# USB.net
KiCad netlist of a schematic drawn in Altium Designer
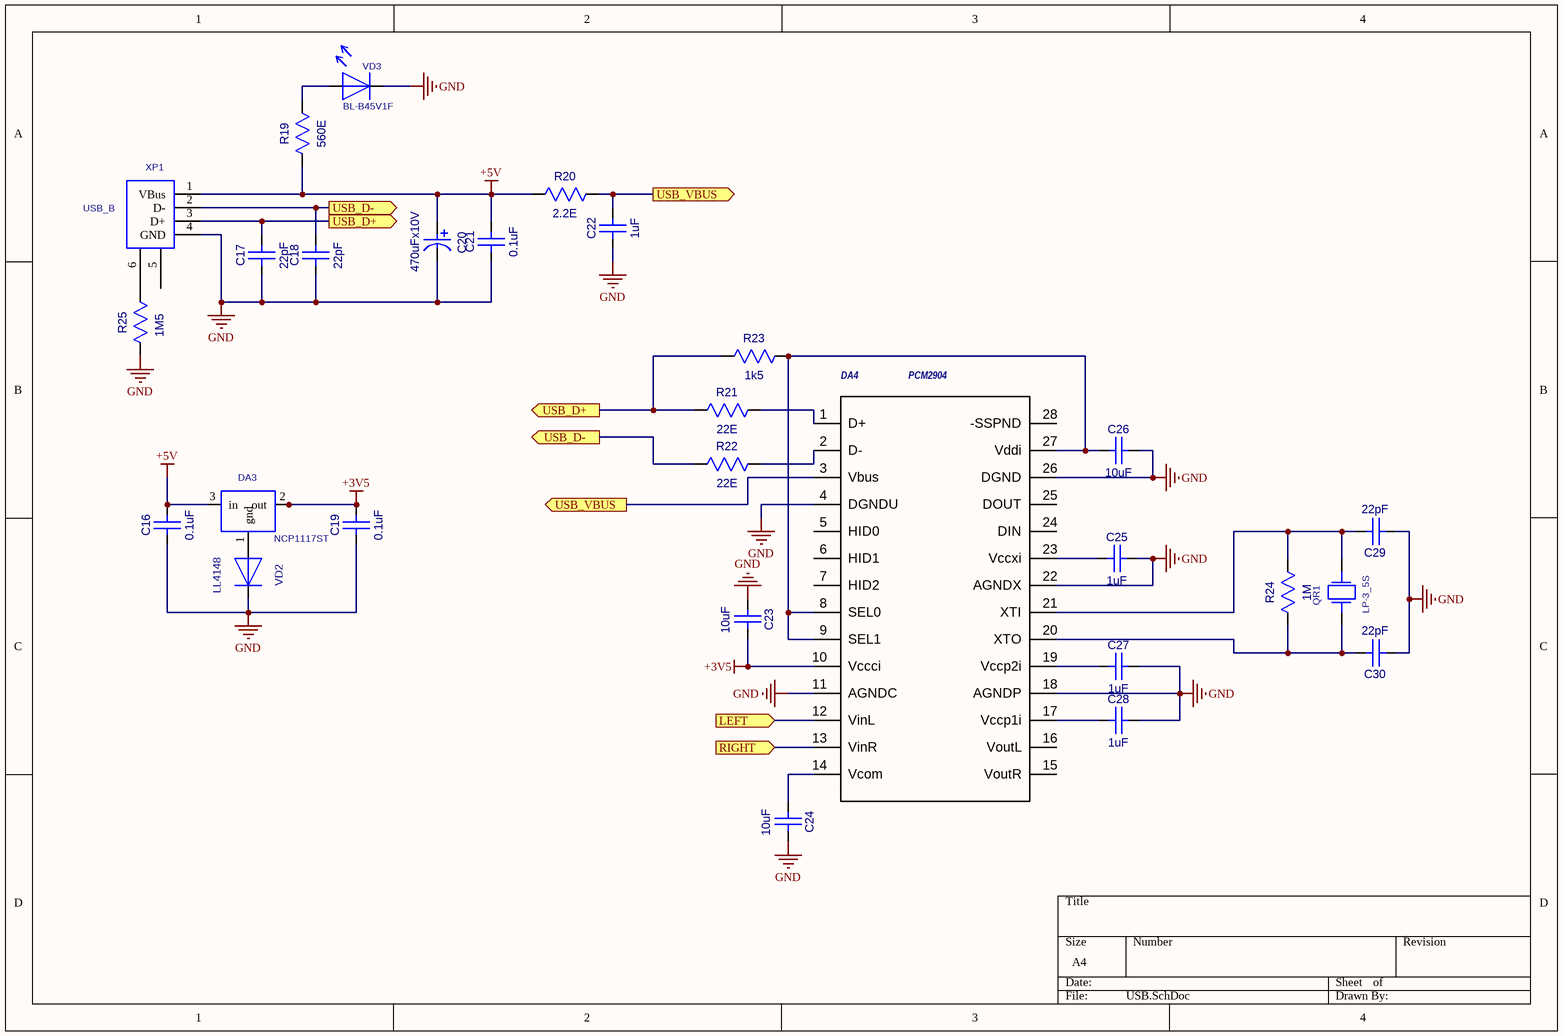
[diagram p0: USB.SchDoc]

(export (version "E")
  (design (tool "Eeschema 10.0.6"))
  (components
    (comp (ref "C16")
      (value "0.1uF")
      (footprint "CC0603-3M")
      (description "CC0603")
      (libsource (lib "Schetchik") (part "CC0603"))
    )
    (comp (ref "C17")
      (value "22pF")
      (footprint "CC0603-3M")
      (description "CC0603")
      (libsource (lib "gprs_modem") (part "CC0603"))
    )
    (comp (ref "C18")
      (value "22pF")
      (footprint "CC0603-3M")
      (description "CC0603")
      (libsource (lib "gprs_modem") (part "CC0603"))
    )
    (comp (ref "C19")
      (value "0.1uF")
      (footprint "CC0603-3M")
      (description "CC0603")
      (libsource (lib "Schetchik") (part "CC0603"))
    )
    (comp (ref "C20")
      (value "470uFx10V")
      (footprint "CC8X3.5")
      (description "CAP0.35")
      (libsource (lib "gprs_modem") (part "CAP0.35"))
    )
    (comp (ref "C21")
      (value "0.1uF")
      (footprint "CC0603-3M")
      (description "CC0603")
      (libsource (lib "gprs_modem") (part "CC0603"))
    )
    (comp (ref "C22")
      (value "1uF")
      (footprint "CC0603-3M")
      (description "CC0603")
      (libsource (lib "gprs_modem") (part "CC0603"))
    )
    (comp (ref "C23")
      (value "10uF")
      (footprint "CC0805-MIDI-2M1")
      (description "CC0805")
      (libsource (lib "gprs_modem") (part "CC0805"))
    )
    (comp (ref "C24")
      (value "10uF")
      (footprint "CC0805-MIDI-2M1")
      (description "CC0805")
      (libsource (lib "gprs_modem") (part "CC0805"))
    )
    (comp (ref "C25")
      (value "1uF")
      (footprint "CC0603-3M")
      (description "CC0603")
      (libsource (lib "") (part "CC0603_1"))
    )
    (comp (ref "C26")
      (value "10uF")
      (footprint "CC0805-MIDI-2M1")
      (description "CC0805")
      (libsource (lib "gprs_modem") (part "CC0805"))
    )
    (comp (ref "C27")
      (value "1uF")
      (footprint "CC0603-3M")
      (description "CC0603")
      (libsource (lib "gprs_modem") (part "CC0603"))
    )
    (comp (ref "C28")
      (value "1uF")
      (footprint "CC0603-3M")
      (description "CC0603")
      (libsource (lib "gprs_modem") (part "CC0603"))
    )
    (comp (ref "C29")
      (value "22pF")
      (footprint "CC0603-3M")
      (description "CC0603")
      (libsource (lib "gprs_modem") (part "CC0603"))
    )
    (comp (ref "C30")
      (value "22pF")
      (footprint "CC0603-3M")
      (description "CC0603")
      (libsource (lib "gprs_modem") (part "CC0603"))
    )
    (comp (ref "DA3")
      (value "NCP1117ST")
      (footprint "SOT-223")
      (libsource (lib "Schetchik") (part "NCP1117ST"))
    )
    (comp (ref "DA4") (value "PCM2904") (footprint "TSSOP28") (libsource (lib "*") (part "PCM2904")))
    (comp (ref "QR1")
      (value "LP-3_5S")
      (footprint "LP_CUARC")
      (libsource (lib "gprs_modem") (part "LP-3_5S"))
    )
    (comp (ref "R19")
      (value "560E")
      (footprint "RC0603-3M")
      (description "RC0603")
      (libsource (lib "gprs_modem") (part "RC0603"))
    )
    (comp (ref "R20")
      (value "2.2E")
      (footprint "RC0805_IPC_NOM")
      (description "RC0805")
      (libsource (lib "gprs_modem") (part "RC0805"))
    )
    (comp (ref "R21")
      (value "22E")
      (footprint "RC0603-3M")
      (description "RC0603")
      (libsource (lib "gprs_modem") (part "RC0603"))
    )
    (comp (ref "R22")
      (value "22E")
      (footprint "RC0603-3M")
      (description "RC0603")
      (libsource (lib "gprs_modem") (part "RC0603"))
    )
    (comp (ref "R23")
      (value "1k5")
      (footprint "RC0603-3M")
      (description "RC0603")
      (libsource (lib "gprs_modem") (part "RC0603"))
    )
    (comp (ref "R24")
      (value "1M")
      (footprint "RC0603-3M")
      (description "RC0603")
      (libsource (lib "gprs_modem") (part "RC0603"))
    )
    (comp (ref "R25")
      (value "1M5")
      (footprint "RC1206-2M")
      (description "RC1206")
      (libsource (lib "gprs_modem") (part "RC1206"))
    )
    (comp (ref "VD2") (value "LL4148") (footprint "SOD-80") (libsource (lib "gprs_modem") (part "LL4148")))
    (comp (ref "VD3")
      (value "BL-B45V1F")
      (footprint "LED3")
      (description "LED_3")
      (libsource (lib "gprs_modem") (part "LED_3"))
    )
    (comp (ref "XP1") (value "USB_B") (footprint "USB-B") (libsource (lib "gprs_modem") (part "USB_B")))
  )
  (nets
    (net (code "1") (name "+3V5") (class "Default")
      (node (ref "C19") (pin "2") (pinfunction "B_2") (pintype "passive"))
      (node (ref "C23") (pin "2") (pinfunction "B_2") (pintype "passive"))
      (node (ref "DA3") (pin "2") (pinfunction "out_2") (pintype "passive"))
      (node (ref "DA3") (pin "4") (pintype "passive"))
      (node (ref "DA4") (pin "10") (pinfunction "Vccci_10") (pintype "passive"))
    )
    (net (code "2") (name "+5V") (class "Default")
      (node (ref "C16") (pin "2") (pinfunction "B_2") (pintype "passive"))
      (node (ref "C20") (pin "1") (pintype "passive"))
      (node (ref "C21") (pin "2") (pinfunction "B_2") (pintype "passive"))
      (node (ref "DA3") (pin "3") (pinfunction "in_3") (pintype "passive"))
      (node (ref "R19") (pin "1") (pinfunction "A_1") (pintype "passive"))
      (node (ref "R20") (pin "1") (pinfunction "A_1") (pintype "passive"))
      (node (ref "XP1") (pin "1") (pinfunction "VBus_1") (pintype "passive"))
    )
    (net (code "3") (name "/LEFT") (class "Default")
      (node (ref "DA4") (pin "12") (pinfunction "VinL_12") (pintype "passive"))
    )
    (net (code "4") (name "/RIGHT") (class "Default")
      (node (ref "DA4") (pin "13") (pinfunction "VinR_13") (pintype "passive"))
    )
    (net (code "5") (name "/USB_D+") (class "Default")
      (node (ref "C17") (pin "2") (pinfunction "B_2") (pintype "passive"))
      (node (ref "R21") (pin "1") (pinfunction "A_1") (pintype "passive"))
      (node (ref "R23") (pin "1") (pinfunction "A_1") (pintype "passive"))
      (node (ref "XP1") (pin "3") (pinfunction "D+_3") (pintype "passive"))
    )
    (net (code "6") (name "/USB_D-") (class "Default")
      (node (ref "C18") (pin "2") (pinfunction "B_2") (pintype "passive"))
      (node (ref "R22") (pin "1") (pinfunction "A_1") (pintype "passive"))
      (node (ref "XP1") (pin "2") (pinfunction "D-_2") (pintype "passive"))
    )
    (net (code "7") (name "/USB_VBUS") (class "Default")
      (node (ref "C22") (pin "2") (pinfunction "B_2") (pintype "passive"))
      (node (ref "DA4") (pin "3") (pinfunction "Vbus_3") (pintype "passive"))
      (node (ref "R20") (pin "2") (pinfunction "B_2") (pintype "passive"))
    )
    (net (code "8") (name "GND") (class "Default")
      (node (ref "C16") (pin "1") (pinfunction "A_1") (pintype "passive"))
      (node (ref "C17") (pin "1") (pinfunction "A_1") (pintype "passive"))
      (node (ref "C18") (pin "1") (pinfunction "A_1") (pintype "passive"))
      (node (ref "C19") (pin "1") (pinfunction "A_1") (pintype "passive"))
      (node (ref "C20") (pin "2") (pintype "passive"))
      (node (ref "C21") (pin "1") (pinfunction "A_1") (pintype "passive"))
      (node (ref "C22") (pin "1") (pinfunction "A_1") (pintype "passive"))
      (node (ref "C23") (pin "1") (pinfunction "A_1") (pintype "passive"))
      (node (ref "C24") (pin "2") (pinfunction "B_2") (pintype "passive"))
      (node (ref "C25") (pin "2") (pinfunction "B_2") (pintype "passive"))
      (node (ref "C26") (pin "2") (pinfunction "B_2") (pintype "passive"))
      (node (ref "C27") (pin "2") (pinfunction "B_2") (pintype "passive"))
      (node (ref "C28") (pin "2") (pinfunction "B_2") (pintype "passive"))
      (node (ref "C29") (pin "1") (pinfunction "A_1") (pintype "passive"))
      (node (ref "C30") (pin "1") (pinfunction "A_1") (pintype "passive"))
      (node (ref "DA4") (pin "11") (pinfunction "AGNDC_11") (pintype "passive"))
      (node (ref "DA4") (pin "18") (pinfunction "AGNDP_18") (pintype "passive"))
      (node (ref "DA4") (pin "22") (pinfunction "AGNDX_22") (pintype "passive"))
      (node (ref "DA4") (pin "26") (pinfunction "DGND_26") (pintype "passive"))
      (node (ref "DA4") (pin "4") (pinfunction "DGNDU_4") (pintype "passive"))
      (node (ref "R25") (pin "1") (pinfunction "A_1") (pintype "passive"))
      (node (ref "VD2") (pin "2") (pinfunction "+_2") (pintype "passive"))
      (node (ref "VD3") (pin "1") (pintype "passive"))
      (node (ref "XP1") (pin "4") (pinfunction "GND_4") (pintype "passive"))
    )
    (net (code "9") (name "Net-(C24-A)") (class "Default")
      (node (ref "C24") (pin "1") (pinfunction "A_1") (pintype "passive"))
      (node (ref "DA4") (pin "14") (pinfunction "Vcom_14") (pintype "passive"))
    )
    (net (code "10") (name "Net-(C25-A)") (class "Default")
      (node (ref "C25") (pin "1") (pinfunction "A_1") (pintype "passive"))
      (node (ref "DA4") (pin "23") (pinfunction "Vccxi_23") (pintype "passive"))
    )
    (net (code "11") (name "Net-(C26-A)") (class "Default")
      (node (ref "C26") (pin "1") (pinfunction "A_1") (pintype "passive"))
      (node (ref "DA4") (pin "27") (pinfunction "Vddi_27") (pintype "passive"))
      (node (ref "DA4") (pin "8") (pinfunction "SEL0_8") (pintype "passive"))
      (node (ref "DA4") (pin "9") (pinfunction "SEL1_9") (pintype "passive"))
      (node (ref "R23") (pin "2") (pinfunction "B_2") (pintype "passive"))
    )
    (net (code "12") (name "Net-(C27-A)") (class "Default")
      (node (ref "C27") (pin "1") (pinfunction "A_1") (pintype "passive"))
      (node (ref "DA4") (pin "19") (pinfunction "Vccp2i_19") (pintype "passive"))
    )
    (net (code "13") (name "Net-(C28-A)") (class "Default")
      (node (ref "C28") (pin "1") (pinfunction "A_1") (pintype "passive"))
      (node (ref "DA4") (pin "17") (pinfunction "Vccp1i_17") (pintype "passive"))
    )
    (net (code "14") (name "Net-(C29-B)") (class "Default")
      (node (ref "C29") (pin "2") (pinfunction "B_2") (pintype "passive"))
      (node (ref "DA4") (pin "21") (pinfunction "XTI_21") (pintype "passive"))
      (node (ref "QR1") (pin "2") (pintype "passive"))
      (node (ref "R24") (pin "2") (pinfunction "B_2") (pintype "passive"))
    )
    (net (code "15") (name "Net-(C30-B)") (class "Default")
      (node (ref "C30") (pin "2") (pinfunction "B_2") (pintype "passive"))
      (node (ref "DA4") (pin "20") (pinfunction "XTO_20") (pintype "passive"))
      (node (ref "QR1") (pin "1") (pintype "passive"))
      (node (ref "R24") (pin "1") (pinfunction "A_1") (pintype "passive"))
    )
    (net (code "16") (name "Net-(DA3-gnd)") (class "Default")
      (node (ref "DA3") (pin "1") (pinfunction "gnd_1") (pintype "passive"))
      (node (ref "VD2") (pin "1") (pinfunction "-_1") (pintype "passive"))
    )
    (net (code "17") (name "Net-(DA4-D+)") (class "Default")
      (node (ref "DA4") (pin "1") (pinfunction "D+_1") (pintype "passive"))
      (node (ref "R21") (pin "2") (pinfunction "B_2") (pintype "passive"))
    )
    (net (code "18") (name "Net-(DA4-D-)") (class "Default")
      (node (ref "DA4") (pin "2") (pinfunction "D-_2") (pintype "passive"))
      (node (ref "R22") (pin "2") (pinfunction "B_2") (pintype "passive"))
    )
    (net (code "19") (name "Net-(R19-B)") (class "Default")
      (node (ref "R19") (pin "2") (pinfunction "B_2") (pintype "passive"))
      (node (ref "VD3") (pin "2") (pintype "passive"))
    )
    (net (code "20") (name "Net-(R25-B)") (class "Default")
      (node (ref "R25") (pin "2") (pinfunction "B_2") (pintype "passive"))
      (node (ref "XP1") (pin "6") (pintype "passive"))
    )
    (net (code "21") (name "unconnected-(DA4--SSPND-Pad28)") (class "Default")
      (node (ref "DA4") (pin "28") (pinfunction "-SSPND_28") (pintype "passive"))
    )
    (net (code "22") (name "unconnected-(DA4-DIN-Pad24)") (class "Default")
      (node (ref "DA4") (pin "24") (pinfunction "DIN_24") (pintype "passive"))
    )
    (net (code "23") (name "unconnected-(DA4-DOUT-Pad25)") (class "Default")
      (node (ref "DA4") (pin "25") (pinfunction "DOUT_25") (pintype "passive"))
    )
    (net (code "24") (name "unconnected-(DA4-HID0-Pad5)") (class "Default")
      (node (ref "DA4") (pin "5") (pinfunction "HID0_5") (pintype "passive"))
    )
    (net (code "25") (name "unconnected-(DA4-HID1-Pad6)") (class "Default")
      (node (ref "DA4") (pin "6") (pinfunction "HID1_6") (pintype "passive"))
    )
    (net (code "26") (name "unconnected-(DA4-HID2-Pad7)") (class "Default")
      (node (ref "DA4") (pin "7") (pinfunction "HID2_7") (pintype "passive"))
    )
    (net (code "27") (name "unconnected-(DA4-VoutL-Pad16)") (class "Default")
      (node (ref "DA4") (pin "16") (pinfunction "VoutL_16") (pintype "passive"))
    )
    (net (code "28") (name "unconnected-(DA4-VoutR-Pad15)") (class "Default")
      (node (ref "DA4") (pin "15") (pinfunction "VoutR_15") (pintype "passive"))
    )
    (net (code "29") (name "unconnected-(XP1-Pad5)") (class "Default")
      (node (ref "XP1") (pin "5") (pintype "passive"))
    )
  )
)
